# tubeboard.net
KiCad netlist of a schematic drawn in EAGLE
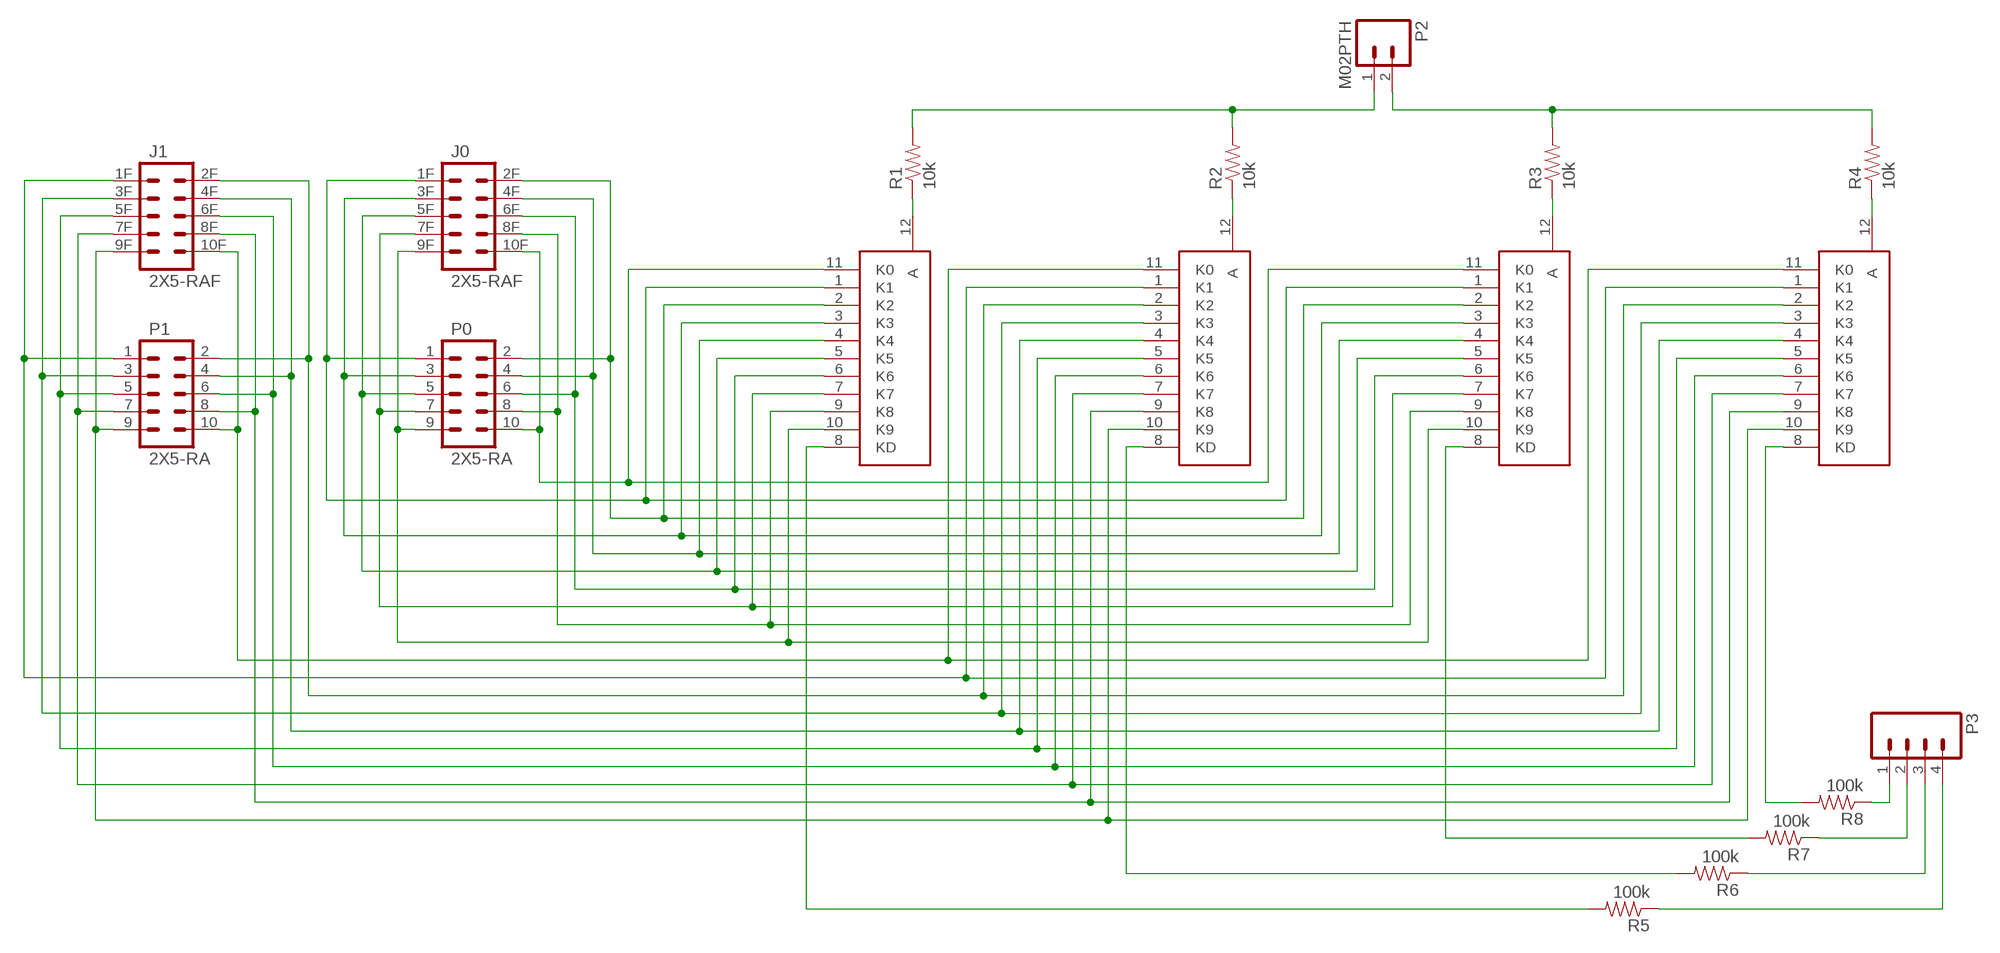
[diagram p0: schematic, sheet 1]

(export (version "E")
  (design (tool "Eeschema 10.0.6"))
  (components
    (comp (ref "J0")
      (value "2X5-RAF")
      (footprint "eagle-import:2X5-RAF")
      (libsource (lib "eagle-import") (part "2X5-RAF"))
    )
    (comp (ref "J1")
      (value "2X5-RAF")
      (footprint "eagle-import:2X5-RAF")
      (libsource (lib "eagle-import") (part "2X5-RAF"))
    )
    (comp (ref "P0")
      (value "2X5-RA")
      (footprint "eagle-import:2X5-RA")
      (libsource (lib "eagle-import") (part "2X5-RA"))
    )
    (comp (ref "P1")
      (value "2X5-RA")
      (footprint "eagle-import:2X5-RA")
      (libsource (lib "eagle-import") (part "2X5-RA"))
    )
    (comp (ref "P2")
      (value "M02PTH")
      (footprint "eagle-import:1X02")
      (libsource (lib "eagle-import") (part "M02PTH"))
    )
    (comp (ref "P3")
      (value "M04PTH")
      (footprint "eagle-import:1X04")
      (libsource (lib "eagle-import") (part "M04PTH"))
    )
    (comp (ref "R1")
      (value "10k")
      (footprint "eagle-import:AXIAL-0.5")
      (libsource (lib "eagle-import") (part "RESISTORPTH-1/2W"))
    )
    (comp (ref "R2")
      (value "10k")
      (footprint "eagle-import:AXIAL-0.5")
      (libsource (lib "eagle-import") (part "RESISTORPTH-1/2W"))
    )
    (comp (ref "R3")
      (value "10k")
      (footprint "eagle-import:AXIAL-0.5")
      (libsource (lib "eagle-import") (part "RESISTORPTH-1/2W"))
    )
    (comp (ref "R4")
      (value "10k")
      (footprint "eagle-import:AXIAL-0.5")
      (libsource (lib "eagle-import") (part "RESISTORPTH-1/2W"))
    )
    (comp (ref "R5")
      (value "100k")
      (footprint "eagle-import:AXIAL-0.5")
      (libsource (lib "eagle-import") (part "RESISTORPTH-1/2W"))
    )
    (comp (ref "R6")
      (value "100k")
      (footprint "eagle-import:AXIAL-0.5")
      (libsource (lib "eagle-import") (part "RESISTORPTH-1/2W"))
    )
    (comp (ref "R7")
      (value "100k")
      (footprint "eagle-import:AXIAL-0.5")
      (libsource (lib "eagle-import") (part "RESISTORPTH-1/2W"))
    )
    (comp (ref "R8")
      (value "100k")
      (footprint "eagle-import:AXIAL-0.5")
      (libsource (lib "eagle-import") (part "RESISTORPTH-1/2W"))
    )
    (comp (ref "V0")
      (value "IN-8-2-GRID")
      (footprint "eagle-import:IN-8-2-GRID")
      (libsource (lib "eagle-import") (part "IN-8-2-GRID"))
    )
    (comp (ref "V1")
      (value "IN-8-2-GRID")
      (footprint "eagle-import:IN-8-2-GRID")
      (libsource (lib "eagle-import") (part "IN-8-2-GRID"))
    )
    (comp (ref "V2")
      (value "IN-8-2-GRID")
      (footprint "eagle-import:IN-8-2-GRID")
      (libsource (lib "eagle-import") (part "IN-8-2-GRID"))
    )
    (comp (ref "V3")
      (value "IN-8-2-GRID")
      (footprint "eagle-import:IN-8-2-GRID")
      (libsource (lib "eagle-import") (part "IN-8-2-GRID"))
    )
  )
  (nets
    (net (code "1") (name "Net-(J0-1)") (class "Default")
      (node (ref "J0") (pin "1F") (pinfunction "1_1F") (pintype "passive"))
      (node (ref "P0") (pin "1") (pinfunction "1_1") (pintype "passive"))
      (node (ref "V0") (pin "1") (pinfunction "K1_1") (pintype "input"))
      (node (ref "V2") (pin "1") (pinfunction "K1_1") (pintype "input"))
    )
    (net (code "2") (name "Net-(J0-2)") (class "Default")
      (node (ref "J0") (pin "2F") (pinfunction "2_2F") (pintype "passive"))
      (node (ref "P0") (pin "2") (pinfunction "2_2") (pintype "passive"))
      (node (ref "V0") (pin "2") (pinfunction "K2_2") (pintype "input"))
      (node (ref "V2") (pin "2") (pinfunction "K2_2") (pintype "input"))
    )
    (net (code "3") (name "Net-(J0-3)") (class "Default")
      (node (ref "J0") (pin "3F") (pinfunction "3_3F") (pintype "passive"))
      (node (ref "P0") (pin "3") (pinfunction "3_3") (pintype "passive"))
      (node (ref "V0") (pin "3") (pinfunction "K3_3") (pintype "input"))
      (node (ref "V2") (pin "3") (pinfunction "K3_3") (pintype "input"))
    )
    (net (code "4") (name "Net-(J0-4)") (class "Default")
      (node (ref "J0") (pin "4F") (pinfunction "4_4F") (pintype "passive"))
      (node (ref "P0") (pin "4") (pinfunction "4_4") (pintype "passive"))
      (node (ref "V0") (pin "4") (pinfunction "K4_4") (pintype "input"))
      (node (ref "V2") (pin "4") (pinfunction "K4_4") (pintype "input"))
    )
    (net (code "5") (name "Net-(J0-5)") (class "Default")
      (node (ref "J0") (pin "5F") (pinfunction "5_5F") (pintype "passive"))
      (node (ref "P0") (pin "5") (pinfunction "5_5") (pintype "passive"))
      (node (ref "V0") (pin "5") (pinfunction "K5_5") (pintype "input"))
      (node (ref "V2") (pin "5") (pinfunction "K5_5") (pintype "input"))
    )
    (net (code "6") (name "Net-(J0-6)") (class "Default")
      (node (ref "J0") (pin "6F") (pinfunction "6_6F") (pintype "passive"))
      (node (ref "P0") (pin "6") (pinfunction "6_6") (pintype "passive"))
      (node (ref "V0") (pin "6") (pinfunction "K6_6") (pintype "input"))
      (node (ref "V2") (pin "6") (pinfunction "K6_6") (pintype "input"))
    )
    (net (code "7") (name "Net-(J0-7)") (class "Default")
      (node (ref "J0") (pin "7F") (pinfunction "7_7F") (pintype "passive"))
      (node (ref "P0") (pin "7") (pinfunction "7_7") (pintype "passive"))
      (node (ref "V0") (pin "7") (pinfunction "K7_7") (pintype "input"))
      (node (ref "V2") (pin "7") (pinfunction "K7_7") (pintype "input"))
    )
    (net (code "8") (name "Net-(J0-8)") (class "Default")
      (node (ref "J0") (pin "8F") (pinfunction "8_8F") (pintype "passive"))
      (node (ref "P0") (pin "8") (pinfunction "8_8") (pintype "passive"))
      (node (ref "V0") (pin "9") (pinfunction "K8_9") (pintype "input"))
      (node (ref "V2") (pin "9") (pinfunction "K8_9") (pintype "input"))
    )
    (net (code "9") (name "Net-(J0-9)") (class "Default")
      (node (ref "J0") (pin "9F") (pinfunction "9_9F") (pintype "passive"))
      (node (ref "P0") (pin "9") (pinfunction "9_9") (pintype "passive"))
      (node (ref "V0") (pin "10") (pinfunction "K9_10") (pintype "input"))
      (node (ref "V2") (pin "10") (pinfunction "K9_10") (pintype "input"))
    )
    (net (code "10") (name "Net-(J0-10)") (class "Default")
      (node (ref "J0") (pin "10F") (pinfunction "10_10F") (pintype "passive"))
      (node (ref "P0") (pin "10") (pinfunction "10_10") (pintype "passive"))
      (node (ref "V0") (pin "11") (pinfunction "K0_11") (pintype "input"))
      (node (ref "V2") (pin "11") (pinfunction "K0_11") (pintype "input"))
    )
    (net (code "11") (name "Net-(J1-1)") (class "Default")
      (node (ref "J1") (pin "1F") (pinfunction "1_1F") (pintype "passive"))
      (node (ref "P1") (pin "1") (pinfunction "1_1") (pintype "passive"))
      (node (ref "V1") (pin "1") (pinfunction "K1_1") (pintype "input"))
      (node (ref "V3") (pin "1") (pinfunction "K1_1") (pintype "input"))
    )
    (net (code "12") (name "Net-(J1-2)") (class "Default")
      (node (ref "J1") (pin "2F") (pinfunction "2_2F") (pintype "passive"))
      (node (ref "P1") (pin "2") (pinfunction "2_2") (pintype "passive"))
      (node (ref "V1") (pin "2") (pinfunction "K2_2") (pintype "input"))
      (node (ref "V3") (pin "2") (pinfunction "K2_2") (pintype "input"))
    )
    (net (code "13") (name "Net-(J1-3)") (class "Default")
      (node (ref "J1") (pin "3F") (pinfunction "3_3F") (pintype "passive"))
      (node (ref "P1") (pin "3") (pinfunction "3_3") (pintype "passive"))
      (node (ref "V1") (pin "3") (pinfunction "K3_3") (pintype "input"))
      (node (ref "V3") (pin "3") (pinfunction "K3_3") (pintype "input"))
    )
    (net (code "14") (name "Net-(J1-4)") (class "Default")
      (node (ref "J1") (pin "4F") (pinfunction "4_4F") (pintype "passive"))
      (node (ref "P1") (pin "4") (pinfunction "4_4") (pintype "passive"))
      (node (ref "V1") (pin "4") (pinfunction "K4_4") (pintype "input"))
      (node (ref "V3") (pin "4") (pinfunction "K4_4") (pintype "input"))
    )
    (net (code "15") (name "Net-(J1-5)") (class "Default")
      (node (ref "J1") (pin "5F") (pinfunction "5_5F") (pintype "passive"))
      (node (ref "P1") (pin "5") (pinfunction "5_5") (pintype "passive"))
      (node (ref "V1") (pin "5") (pinfunction "K5_5") (pintype "input"))
      (node (ref "V3") (pin "5") (pinfunction "K5_5") (pintype "input"))
    )
    (net (code "16") (name "Net-(J1-6)") (class "Default")
      (node (ref "J1") (pin "6F") (pinfunction "6_6F") (pintype "passive"))
      (node (ref "P1") (pin "6") (pinfunction "6_6") (pintype "passive"))
      (node (ref "V1") (pin "6") (pinfunction "K6_6") (pintype "input"))
      (node (ref "V3") (pin "6") (pinfunction "K6_6") (pintype "input"))
    )
    (net (code "17") (name "Net-(J1-7)") (class "Default")
      (node (ref "J1") (pin "7F") (pinfunction "7_7F") (pintype "passive"))
      (node (ref "P1") (pin "7") (pinfunction "7_7") (pintype "passive"))
      (node (ref "V1") (pin "7") (pinfunction "K7_7") (pintype "input"))
      (node (ref "V3") (pin "7") (pinfunction "K7_7") (pintype "input"))
    )
    (net (code "18") (name "Net-(J1-8)") (class "Default")
      (node (ref "J1") (pin "8F") (pinfunction "8_8F") (pintype "passive"))
      (node (ref "P1") (pin "8") (pinfunction "8_8") (pintype "passive"))
      (node (ref "V1") (pin "9") (pinfunction "K8_9") (pintype "input"))
      (node (ref "V3") (pin "9") (pinfunction "K8_9") (pintype "input"))
    )
    (net (code "19") (name "Net-(J1-9)") (class "Default")
      (node (ref "J1") (pin "9F") (pinfunction "9_9F") (pintype "passive"))
      (node (ref "P1") (pin "9") (pinfunction "9_9") (pintype "passive"))
      (node (ref "V1") (pin "10") (pinfunction "K9_10") (pintype "input"))
      (node (ref "V3") (pin "10") (pinfunction "K9_10") (pintype "input"))
    )
    (net (code "20") (name "Net-(J1-10)") (class "Default")
      (node (ref "J1") (pin "10F") (pinfunction "10_10F") (pintype "passive"))
      (node (ref "P1") (pin "10") (pinfunction "10_10") (pintype "passive"))
      (node (ref "V1") (pin "11") (pinfunction "K0_11") (pintype "input"))
      (node (ref "V3") (pin "11") (pinfunction "K0_11") (pintype "input"))
    )
    (net (code "21") (name "Net-(R1-1)") (class "Default")
      (node (ref "R1") (pin "P$1") (pinfunction "1_P$1") (pintype "passive"))
      (node (ref "V0") (pin "12") (pinfunction "A_12") (pintype "input"))
    )
    (net (code "22") (name "Net-(R1-2)") (class "Default")
      (node (ref "P2") (pin "1") (pinfunction "1_1") (pintype "passive"))
      (node (ref "R1") (pin "P$2") (pinfunction "2_P$2") (pintype "passive"))
      (node (ref "R2") (pin "P$2") (pinfunction "2_P$2") (pintype "passive"))
    )
    (net (code "23") (name "Net-(R2-1)") (class "Default")
      (node (ref "R2") (pin "P$1") (pinfunction "1_P$1") (pintype "passive"))
      (node (ref "V1") (pin "12") (pinfunction "A_12") (pintype "input"))
    )
    (net (code "24") (name "Net-(R3-1)") (class "Default")
      (node (ref "R3") (pin "P$1") (pinfunction "1_P$1") (pintype "passive"))
      (node (ref "V2") (pin "12") (pinfunction "A_12") (pintype "input"))
    )
    (net (code "25") (name "Net-(R3-2)") (class "Default")
      (node (ref "P2") (pin "2") (pinfunction "2_2") (pintype "passive"))
      (node (ref "R3") (pin "P$2") (pinfunction "2_P$2") (pintype "passive"))
      (node (ref "R4") (pin "P$2") (pinfunction "2_P$2") (pintype "passive"))
    )
    (net (code "26") (name "Net-(R4-1)") (class "Default")
      (node (ref "R4") (pin "P$1") (pinfunction "1_P$1") (pintype "passive"))
      (node (ref "V3") (pin "12") (pinfunction "A_12") (pintype "input"))
    )
    (net (code "27") (name "Net-(R5-1)") (class "Default")
      (node (ref "P3") (pin "4") (pinfunction "4_4") (pintype "passive"))
      (node (ref "R5") (pin "P$1") (pinfunction "1_P$1") (pintype "passive"))
    )
    (net (code "28") (name "Net-(R5-2)") (class "Default")
      (node (ref "R5") (pin "P$2") (pinfunction "2_P$2") (pintype "passive"))
      (node (ref "V0") (pin "8") (pinfunction "KD_8") (pintype "input"))
    )
    (net (code "29") (name "Net-(R6-1)") (class "Default")
      (node (ref "P3") (pin "3") (pinfunction "3_3") (pintype "passive"))
      (node (ref "R6") (pin "P$1") (pinfunction "1_P$1") (pintype "passive"))
    )
    (net (code "30") (name "Net-(R6-2)") (class "Default")
      (node (ref "R6") (pin "P$2") (pinfunction "2_P$2") (pintype "passive"))
      (node (ref "V1") (pin "8") (pinfunction "KD_8") (pintype "input"))
    )
    (net (code "31") (name "Net-(R7-1)") (class "Default")
      (node (ref "P3") (pin "2") (pinfunction "2_2") (pintype "passive"))
      (node (ref "R7") (pin "P$1") (pinfunction "1_P$1") (pintype "passive"))
    )
    (net (code "32") (name "Net-(R7-2)") (class "Default")
      (node (ref "R7") (pin "P$2") (pinfunction "2_P$2") (pintype "passive"))
      (node (ref "V2") (pin "8") (pinfunction "KD_8") (pintype "input"))
    )
    (net (code "33") (name "Net-(R8-1)") (class "Default")
      (node (ref "P3") (pin "1") (pinfunction "1_1") (pintype "passive"))
      (node (ref "R8") (pin "P$1") (pinfunction "1_P$1") (pintype "passive"))
    )
    (net (code "34") (name "Net-(R8-2)") (class "Default")
      (node (ref "R8") (pin "P$2") (pinfunction "2_P$2") (pintype "passive"))
      (node (ref "V3") (pin "8") (pinfunction "KD_8") (pintype "input"))
    )
  )
)
